# Sheet1.net
KiCad netlist of a schematic drawn in Altium Designer
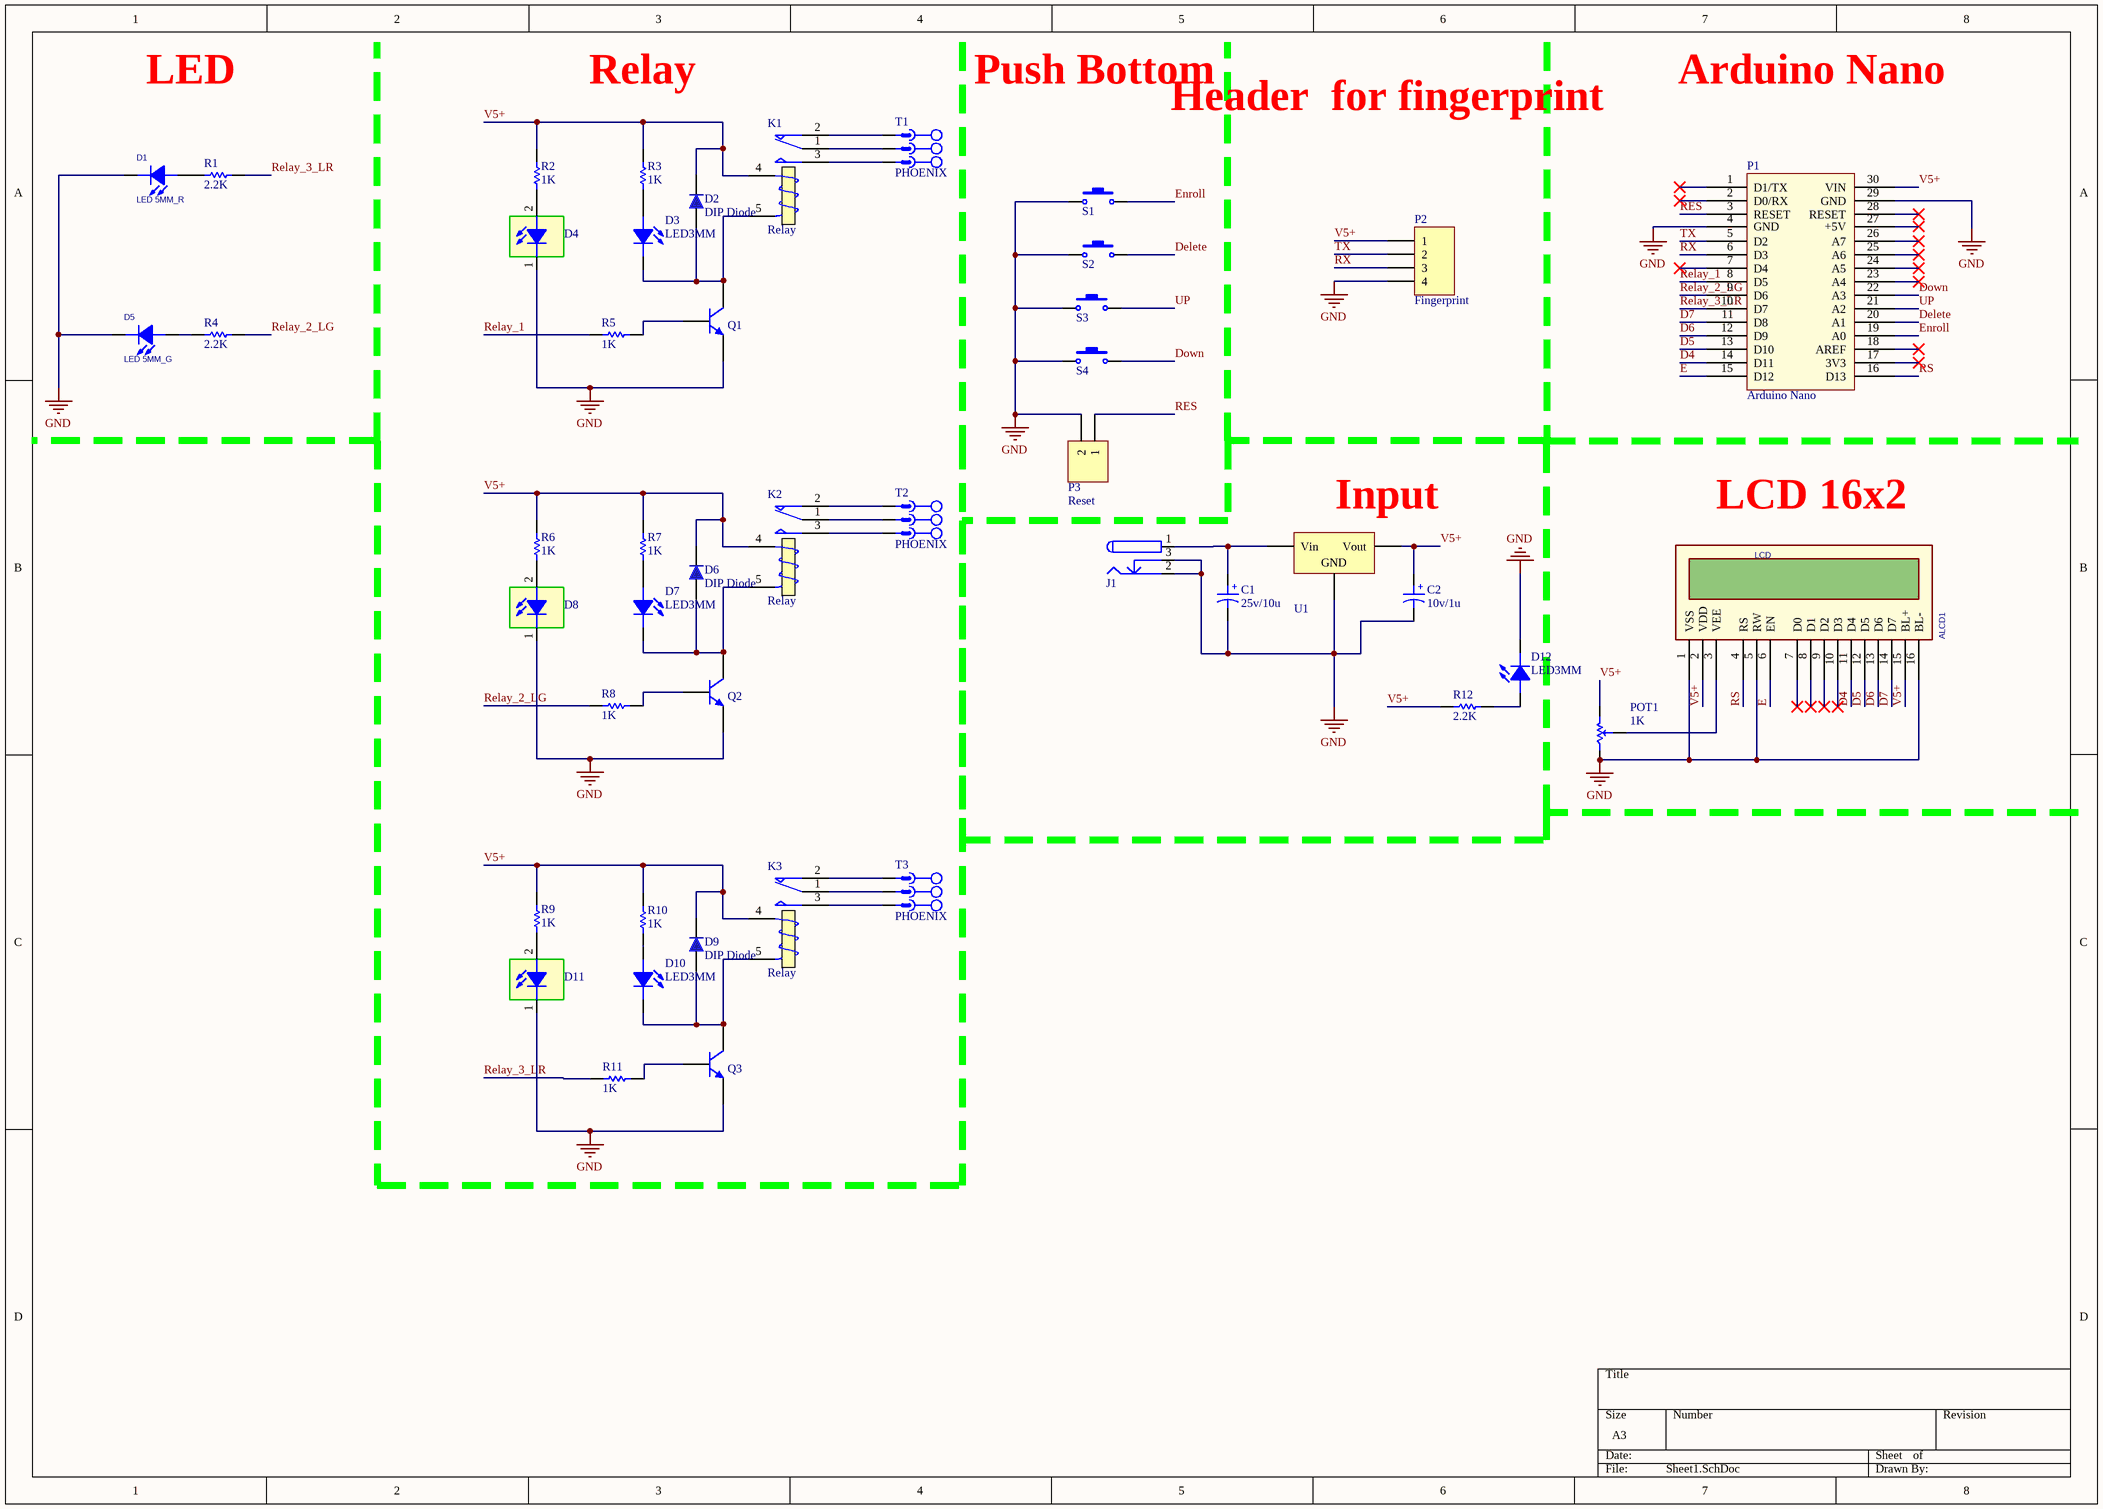
[diagram p0: Sheet1.SchDoc]

(export (version "E")
  (design (tool "Eeschema 10.0.6"))
  (components
    (comp (ref "ALCD1")
      (value "LCD")
      (footprint "LCD_2X16 BLUE - 2.5mm")
      (description "Alphanumic LCD")
      (fields (field (name "DESIGNER") "Abbas Basereh"))
      (libsource (lib "Altium") (part "LCD"))
    )
    (comp (ref "C1")
      (value "25v/10u")
      (footprint "Cap electrolitic radial 5x11-2")
      (description "Cap electrolitic radial")
      (fields (field (name "DESIGNER") "Abbas Basereh"))
      (libsource (lib "Altium") (part "Cap ELECTROLITIC TOTAL SIZE"))
    )
    (comp (ref "C2")
      (value "10v/1u")
      (footprint "Cap electrolitic radial 5x11-2")
      (description "Cap electrolitic radial")
      (fields (field (name "DESIGNER") "Abbas Basereh"))
      (libsource (lib "Altium") (part "Cap ELECTROLITIC TOTAL SIZE"))
    )
    (comp (ref "D1")
      (value "LED 5MM_R")
      (footprint "LED5MM_RED")
      (description "Light Emitting Diode")
      (fields (field (name "DESIGNER") "Abbas Basereh"))
      (libsource (lib "Altium") (part "LED 5MM"))
    )
    (comp (ref "D2")
      (value "DIP Diode")
      (footprint "Diode 1n4007")
      (description "Diode DIP Package")
      (fields (field (name "PUBLISHER") "Altium Limited"))
      (libsource (lib "Altium") (part "Diode DIP Package"))
    )
    (comp (ref "D3")
      (value "LED3MM")
      (footprint "LED3mm_GRN")
      (description "Light Emitting Diode")
      (fields (field (name "DESIGNER") "Ali Hafizi"))
      (libsource (lib "Altium") (part "LED 3MM"))
    )
    (comp (ref "D4")
      (value "LED SMD 3528")
      (footprint "LED 3528")
      (description "SMD 3528 LED")
      (libsource (lib "Altium") (part "LED SMD 3528"))
    )
    (comp (ref "D5")
      (value "LED 5MM_G")
      (footprint "LED5MM_GRN")
      (description "Light Emitting Diode")
      (fields (field (name "DESIGNER") "Abbas Basereh"))
      (libsource (lib "Altium") (part "LED 5MM"))
    )
    (comp (ref "D6")
      (value "DIP Diode")
      (footprint "Diode 1n4007")
      (description "Diode DIP Package")
      (fields (field (name "PUBLISHER") "Altium Limited"))
      (libsource (lib "Altium") (part "Diode DIP Package"))
    )
    (comp (ref "D7")
      (value "LED3MM")
      (footprint "LED3mm_GRN")
      (description "Light Emitting Diode")
      (fields (field (name "DESIGNER") "Ali Hafizi"))
      (libsource (lib "Altium") (part "LED 3MM"))
    )
    (comp (ref "D8")
      (value "LED SMD 3528")
      (footprint "LED 3528")
      (description "SMD 3528 LED")
      (libsource (lib "Altium") (part "LED SMD 3528"))
    )
    (comp (ref "D9")
      (value "DIP Diode")
      (footprint "Diode 1n4007")
      (description "Diode DIP Package")
      (fields (field (name "PUBLISHER") "Altium Limited"))
      (libsource (lib "Altium") (part "Diode DIP Package"))
    )
    (comp (ref "D10")
      (value "LED3MM")
      (footprint "LED3mm_GRN")
      (description "Light Emitting Diode")
      (fields (field (name "DESIGNER") "Ali Hafizi"))
      (libsource (lib "Altium") (part "LED 3MM"))
    )
    (comp (ref "D11")
      (value "LED SMD 3528")
      (footprint "LED 3528")
      (description "SMD 3528 LED")
      (libsource (lib "Altium") (part "LED SMD 3528"))
    )
    (comp (ref "D12")
      (value "LED3MM")
      (footprint "LED5MM_RED")
      (description "Light Emitting Diode")
      (fields (field (name "DESIGNER") "Ali Hafizi"))
      (libsource (lib "Altium") (part "LED 3MM"))
    )
    (comp (ref "J1")
      (value "DC Power Jack")
      (footprint "DC Power Jack 1")
      (description "DC Power Jack. Center Pin 2.5mm. Diameter: 5.7mm")
      (fields (field (name "DESIGNER") "Ali Hafizi"))
      (libsource (lib "Altium") (part "DC Power Jack"))
    )
    (comp (ref "K1")
      (value "Relay")
      (footprint "Relay 15.40x12.10x13.10")
      (description "Relay_SPDT POWER NEEDLE")
      (fields (field (name "DESIGNER") "Ali Hafizi"))
      (libsource (lib "Altium") (part "RELAY General"))
    )
    (comp (ref "K2")
      (value "Relay")
      (footprint "Relay 15.40x12.10x13.10")
      (description "Relay_SPDT POWER NEEDLE")
      (fields (field (name "DESIGNER") "Ali Hafizi"))
      (libsource (lib "Altium") (part "RELAY General"))
    )
    (comp (ref "K3")
      (value "Relay")
      (footprint "Relay 15.40x12.10x13.10")
      (description "Relay_SPDT POWER NEEDLE")
      (fields (field (name "DESIGNER") "Ali Hafizi"))
      (libsource (lib "Altium") (part "RELAY General"))
    )
    (comp (ref "P1")
      (value "Arduino Nano")
      (footprint "Arduino Nano")
      (libsource (lib "Arduino") (part "Arduino Nano"))
    )
    (comp (ref "P2")
      (value "Fingerprint")
      (footprint "HDR1X4")
      (description "Header, 4-Pin")
      (fields (field (name "PUBLISHER") "Altium Limited"))
      (libsource (lib "Altium") (part "Header 4"))
    )
    (comp (ref "P3")
      (value "Reset")
      (footprint "HDR1X2")
      (description "Header, 2-Pin")
      (fields (field (name "PUBLISHER") "Altium Limited"))
      (libsource (lib "Altium") (part "Header 2"))
    )
    (comp (ref "POT1")
      (value "1K")
      (footprint "POT 1")
      (description "Variable Resistor")
      (libsource (lib "Altium") (part "POT"))
    )
    (comp (ref "Q1")
      (value "BC547")
      (footprint "TO-92 BENT")
      (description "NPN General-purpose Transistor")
      (fields (field (name "DESIGNER") "Abbas Basereh"))
      (libsource (lib "Altium") (part "BC547"))
    )
    (comp (ref "Q2")
      (value "BC547")
      (footprint "TO-92 BENT")
      (description "NPN General-purpose Transistor")
      (fields (field (name "DESIGNER") "Abbas Basereh"))
      (libsource (lib "Altium") (part "BC547"))
    )
    (comp (ref "Q3")
      (value "BC547")
      (footprint "TO-92 BENT")
      (description "NPN General-purpose Transistor")
      (fields (field (name "DESIGNER") "Abbas Basereh"))
      (libsource (lib "Altium") (part "BC547"))
    )
    (comp (ref "R1")
      (value "2.2K")
      (footprint "Axial 0_25w_2_54mm")
      (description "RES Axial 0.25W")
      (fields (field (name "DESIGNER") "Abbas Basereh"))
      (libsource (lib "Altium") (part "RES Axial 0.25W"))
    )
    (comp (ref "R2")
      (value "1K")
      (footprint "Axial 0_25w_2_54mm")
      (description "RES Axial 0.25W")
      (fields (field (name "DESIGNER") "Abbas Basereh"))
      (libsource (lib "Altium") (part "RES Axial 0.25W"))
    )
    (comp (ref "R3")
      (value "1K")
      (footprint "Axial 0_25w_2_54mm")
      (description "RES Axial 0.25W")
      (fields (field (name "DESIGNER") "Abbas Basereh"))
      (libsource (lib "Altium") (part "RES Axial 0.25W"))
    )
    (comp (ref "R4")
      (value "2.2K")
      (footprint "Axial 0_25w_2_54mm")
      (description "RES Axial 0.25W")
      (fields (field (name "DESIGNER") "Abbas Basereh"))
      (libsource (lib "Altium") (part "RES Axial 0.25W"))
    )
    (comp (ref "R5")
      (value "1K")
      (footprint "Axial 0_25w_2_54mm")
      (description "RES Axial 0.25W")
      (fields (field (name "DESIGNER") "Abbas Basereh"))
      (libsource (lib "Altium") (part "RES Axial 0.25W"))
    )
    (comp (ref "R6")
      (value "1K")
      (footprint "Axial 0_25w_2_54mm")
      (description "RES Axial 0.25W")
      (fields (field (name "DESIGNER") "Abbas Basereh"))
      (libsource (lib "Altium") (part "RES Axial 0.25W"))
    )
    (comp (ref "R7")
      (value "1K")
      (footprint "Axial 0_25w_2_54mm")
      (description "RES Axial 0.25W")
      (fields (field (name "DESIGNER") "Abbas Basereh"))
      (libsource (lib "Altium") (part "RES Axial 0.25W"))
    )
    (comp (ref "R8")
      (value "1K")
      (footprint "Axial 0_25w_2_54mm")
      (description "RES Axial 0.25W")
      (fields (field (name "DESIGNER") "Abbas Basereh"))
      (libsource (lib "Altium") (part "RES Axial 0.25W"))
    )
    (comp (ref "R9")
      (value "1K")
      (footprint "Axial 0_25w_2_54mm")
      (description "RES Axial 0.25W")
      (fields (field (name "DESIGNER") "Abbas Basereh"))
      (libsource (lib "Altium") (part "RES Axial 0.25W"))
    )
    (comp (ref "R10")
      (value "1K")
      (footprint "Axial 0_25w_2_54mm")
      (description "RES Axial 0.25W")
      (fields (field (name "DESIGNER") "Abbas Basereh"))
      (libsource (lib "Altium") (part "RES Axial 0.25W"))
    )
    (comp (ref "R11")
      (value "1K")
      (footprint "Axial 0_25w_2_54mm")
      (description "RES Axial 0.25W")
      (fields (field (name "DESIGNER") "Abbas Basereh"))
      (libsource (lib "Altium") (part "RES Axial 0.25W"))
    )
    (comp (ref "R12")
      (value "2.2K")
      (footprint "Axial 0_25w_2_54mm")
      (description "RES Axial 0.25W")
      (fields (field (name "DESIGNER") "Abbas Basereh"))
      (libsource (lib "Altium") (part "RES Axial 0.25W"))
    )
    (comp (ref "S1")
      (value "Switch PB")
      (footprint "Switch - Push to On")
      (description "Push Button Switch")
      (libsource (lib "Altium") (part "Switch PB"))
    )
    (comp (ref "S2")
      (value "Switch PB")
      (footprint "Switch - Push to On")
      (description "Push Button Switch")
      (libsource (lib "Altium") (part "Switch PB"))
    )
    (comp (ref "S3")
      (value "Switch PB")
      (footprint "Switch - Push to On")
      (description "Push Button Switch")
      (libsource (lib "Altium") (part "Switch PB"))
    )
    (comp (ref "S4")
      (value "Switch PB")
      (footprint "Switch - Push to On")
      (description "Push Button Switch")
      (libsource (lib "Altium") (part "Switch PB"))
    )
    (comp (ref "T1")
      (value "PHOENIX")
      (footprint "MSTBV 2,5/3-G-5")
      (description "3 Pitch: 5 mm Color: green Contact surface: Tin Assembly")
      (fields
        (field (name "MANUFACTURER") "PHOENIX CONTACT")
        (field (name "VOLTAGE") "320 V")
        (field (name "DESIGNER") "ABBAS BASEREH")
      )
      (libsource (lib "Altium") (part "CON_Phoenix_MSTBV_03"))
    )
    (comp (ref "T2")
      (value "PHOENIX")
      (footprint "MSTBV 2,5/3-G-5")
      (description "3 Pitch: 5 mm Color: green Contact surface: Tin Assembly")
      (fields
        (field (name "MANUFACTURER") "PHOENIX CONTACT")
        (field (name "VOLTAGE") "320 V")
        (field (name "DESIGNER") "ABBAS BASEREH")
      )
      (libsource (lib "Altium") (part "CON_Phoenix_MSTBV_03"))
    )
    (comp (ref "T3")
      (value "PHOENIX")
      (footprint "MSTBV 2,5/3-G-5")
      (description "3 Pitch: 5 mm Color: green Contact surface: Tin Assembly")
      (fields
        (field (name "MANUFACTURER") "PHOENIX CONTACT")
        (field (name "VOLTAGE") "320 V")
        (field (name "DESIGNER") "ABBAS BASEREH")
      )
      (libsource (lib "Altium") (part "CON_Phoenix_MSTBV_03"))
    )
    (comp (ref "U1")
      (value "L7805CV")
      (footprint "TO-220 AB with heatsink ya25")
      (description "Linear Voltage Regulator IC Positive FIXED Output 5V 1.5A TO-220AB")
      (fields (field (name "MANUFACTURER") "STMicroelectronics") (field (name "DESIGNER") "Abbas Basereh"))
      (libsource (lib "Altium") (part "L7805CV-Linear Voltage Regulator"))
    )
  )
  (nets
    (net (code "1") (name "/D4") (class "Default")
      (node (ref "ALCD1") (pin "11") (pinfunction "D4_11") (pintype "passive"))
      (node (ref "P1") (pin "14") (pinfunction "D11_14") (pintype "passive"))
    )
    (net (code "2") (name "/D5") (class "Default")
      (node (ref "ALCD1") (pin "12") (pinfunction "D5_12") (pintype "passive"))
      (node (ref "P1") (pin "13") (pinfunction "D10_13") (pintype "passive"))
    )
    (net (code "3") (name "/D6") (class "Default")
      (node (ref "ALCD1") (pin "13") (pinfunction "D6_13") (pintype "passive"))
      (node (ref "P1") (pin "12") (pinfunction "D9_12") (pintype "passive"))
    )
    (net (code "4") (name "/D7") (class "Default")
      (node (ref "ALCD1") (pin "14") (pinfunction "D7_14") (pintype "passive"))
      (node (ref "P1") (pin "11") (pinfunction "D8_11") (pintype "passive"))
    )
    (net (code "5") (name "/Delete") (class "Default")
      (node (ref "P1") (pin "20") (pinfunction "A1_20") (pintype "passive"))
      (node (ref "S2") (pin "2") (pinfunction "2_2") (pintype "passive"))
    )
    (net (code "6") (name "/Down") (class "Default")
      (node (ref "P1") (pin "22") (pinfunction "A3_22") (pintype "passive"))
      (node (ref "S4") (pin "2") (pinfunction "2_2") (pintype "passive"))
    )
    (net (code "7") (name "/E") (class "Default")
      (node (ref "ALCD1") (pin "6") (pinfunction "EN_6") (pintype "passive"))
      (node (ref "P1") (pin "15") (pinfunction "D12_15") (pintype "passive"))
    )
    (net (code "8") (name "/Enroll") (class "Default")
      (node (ref "P1") (pin "19") (pinfunction "A0_19") (pintype "passive"))
      (node (ref "S1") (pin "2") (pinfunction "2_2") (pintype "passive"))
    )
    (net (code "9") (name "/RES") (class "Default")
      (node (ref "P1") (pin "3") (pinfunction "RESET_3") (pintype "passive"))
      (node (ref "P3") (pin "1") (pinfunction "1_1") (pintype "passive"))
    )
    (net (code "10") (name "/RS") (class "Default")
      (node (ref "ALCD1") (pin "4") (pinfunction "RS_4") (pintype "passive"))
      (node (ref "P1") (pin "16") (pinfunction "D13_16") (pintype "passive"))
    )
    (net (code "11") (name "/RX") (class "Default")
      (node (ref "P1") (pin "6") (pinfunction "D3_6") (pintype "passive"))
      (node (ref "P2") (pin "3") (pinfunction "3_3") (pintype "passive"))
    )
    (net (code "12") (name "/Relay_1") (class "Default")
      (node (ref "P1") (pin "8") (pinfunction "D5_8") (pintype "passive"))
      (node (ref "R5") (pin "2") (pinfunction "2_2") (pintype "passive"))
    )
    (net (code "13") (name "/Relay_2_LG") (class "Default")
      (node (ref "P1") (pin "9") (pinfunction "D6_9") (pintype "passive"))
      (node (ref "R4") (pin "2") (pinfunction "2_2") (pintype "passive"))
      (node (ref "R8") (pin "1") (pinfunction "1_1") (pintype "passive"))
    )
    (net (code "14") (name "/Relay_3_LR") (class "Default")
      (node (ref "P1") (pin "10") (pinfunction "D7_10") (pintype "passive"))
      (node (ref "R1") (pin "2") (pinfunction "2_2") (pintype "passive"))
      (node (ref "R11") (pin "2") (pinfunction "2_2") (pintype "passive"))
    )
    (net (code "15") (name "/TX") (class "Default")
      (node (ref "P1") (pin "5") (pinfunction "D2_5") (pintype "passive"))
      (node (ref "P2") (pin "2") (pinfunction "2_2") (pintype "passive"))
    )
    (net (code "16") (name "/UP") (class "Default")
      (node (ref "P1") (pin "21") (pinfunction "A2_21") (pintype "passive"))
      (node (ref "S3") (pin "2") (pinfunction "2_2") (pintype "passive"))
    )
    (net (code "17") (name "/V5+") (class "Default")
      (node (ref "ALCD1") (pin "15") (pinfunction "BL+_15") (pintype "passive"))
      (node (ref "ALCD1") (pin "2") (pinfunction "VDD_2") (pintype "passive"))
      (node (ref "C2") (pin "1") (pinfunction "1_1") (pintype "passive"))
      (node (ref "D2") (pin "2") (pintype "passive"))
      (node (ref "D6") (pin "2") (pintype "passive"))
      (node (ref "D9") (pin "2") (pintype "passive"))
      (node (ref "K1") (pin "4") (pinfunction "T1_4") (pintype "passive"))
      (node (ref "K2") (pin "4") (pinfunction "T1_4") (pintype "passive"))
      (node (ref "K3") (pin "4") (pinfunction "T1_4") (pintype "passive"))
      (node (ref "P1") (pin "30") (pinfunction "VIN_30") (pintype "passive"))
      (node (ref "P2") (pin "1") (pinfunction "1_1") (pintype "passive"))
      (node (ref "POT1") (pin "2") (pinfunction "CW_2") (pintype "passive"))
      (node (ref "R10") (pin "2") (pinfunction "2_2") (pintype "passive"))
      (node (ref "R12") (pin "1") (pinfunction "1_1") (pintype "passive"))
      (node (ref "R2") (pin "2") (pinfunction "2_2") (pintype "passive"))
      (node (ref "R3") (pin "2") (pinfunction "2_2") (pintype "passive"))
      (node (ref "R6") (pin "1") (pinfunction "1_1") (pintype "passive"))
      (node (ref "R7") (pin "1") (pinfunction "1_1") (pintype "passive"))
      (node (ref "R9") (pin "2") (pinfunction "2_2") (pintype "passive"))
      (node (ref "U1") (pin "3") (pinfunction "Vout_3") (pintype "passive"))
    )
    (net (code "18") (name "GND") (class "Default")
      (node (ref "ALCD1") (pin "1") (pinfunction "VSS_1") (pintype "passive"))
      (node (ref "ALCD1") (pin "16") (pinfunction "BL-_16") (pintype "passive"))
      (node (ref "ALCD1") (pin "5") (pinfunction "RW_5") (pintype "passive"))
      (node (ref "C1") (pin "2") (pinfunction "2_2") (pintype "passive"))
      (node (ref "C2") (pin "2") (pinfunction "2_2") (pintype "passive"))
      (node (ref "D1") (pin "2") (pinfunction "CATHODE_2") (pintype "passive"))
      (node (ref "D11") (pin "1") (pinfunction "1_1") (pintype "passive"))
      (node (ref "D12") (pin "2") (pinfunction "CATHODE_2") (pintype "passive"))
      (node (ref "D4") (pin "1") (pinfunction "1_1") (pintype "passive"))
      (node (ref "D5") (pin "2") (pinfunction "CATHODE_2") (pintype "passive"))
      (node (ref "D8") (pin "1") (pinfunction "1_1") (pintype "passive"))
      (node (ref "J1") (pin "2") (pinfunction "2_2") (pintype "power_in"))
      (node (ref "J1") (pin "3") (pinfunction "3_3") (pintype "power_in"))
      (node (ref "P1") (pin "29") (pinfunction "GND_29") (pintype "passive"))
      (node (ref "P1") (pin "4") (pinfunction "GND_4") (pintype "passive"))
      (node (ref "P2") (pin "4") (pinfunction "4_4") (pintype "passive"))
      (node (ref "P3") (pin "2") (pinfunction "2_2") (pintype "passive"))
      (node (ref "POT1") (pin "1") (pinfunction "CCW_1") (pintype "passive"))
      (node (ref "Q1") (pin "3") (pinfunction "E_3") (pintype "passive"))
      (node (ref "Q2") (pin "3") (pinfunction "E_3") (pintype "passive"))
      (node (ref "Q3") (pin "3") (pinfunction "E_3") (pintype "passive"))
      (node (ref "S1") (pin "1") (pinfunction "1_1") (pintype "passive"))
      (node (ref "S2") (pin "1") (pinfunction "1_1") (pintype "passive"))
      (node (ref "S3") (pin "1") (pinfunction "1_1") (pintype "passive"))
      (node (ref "S4") (pin "1") (pinfunction "1_1") (pintype "passive"))
      (node (ref "U1") (pin "2") (pinfunction "GND_2") (pintype "passive"))
    )
    (net (code "19") (name "Net-(ALCD1-VEE)") (class "Default")
      (node (ref "ALCD1") (pin "3") (pinfunction "VEE_3") (pintype "passive"))
      (node (ref "POT1") (pin "3") (pinfunction "SetPoint_3") (pintype "passive"))
    )
    (net (code "20") (name "Net-(D1-ANODE)") (class "Default")
      (node (ref "D1") (pin "1") (pinfunction "ANODE_1") (pintype "passive"))
      (node (ref "R1") (pin "1") (pinfunction "1_1") (pintype "passive"))
    )
    (net (code "21") (name "Net-(D3-ANODE)") (class "Default")
      (node (ref "D3") (pin "1") (pinfunction "ANODE_1") (pintype "passive"))
      (node (ref "R3") (pin "1") (pinfunction "1_1") (pintype "passive"))
    )
    (net (code "22") (name "Net-(D3-CATHODE)") (class "Default")
      (node (ref "D2") (pin "1") (pintype "passive"))
      (node (ref "D3") (pin "2") (pinfunction "CATHODE_2") (pintype "passive"))
      (node (ref "K1") (pin "5") (pinfunction "T2_5") (pintype "passive"))
      (node (ref "Q1") (pin "1") (pinfunction "C_1") (pintype "passive"))
    )
    (net (code "23") (name "Net-(D4-Pad2)") (class "Default")
      (node (ref "D4") (pin "2") (pinfunction "2_2") (pintype "passive"))
      (node (ref "R2") (pin "1") (pinfunction "1_1") (pintype "passive"))
    )
    (net (code "24") (name "Net-(D5-ANODE)") (class "Default")
      (node (ref "D5") (pin "1") (pinfunction "ANODE_1") (pintype "passive"))
      (node (ref "R4") (pin "1") (pinfunction "1_1") (pintype "passive"))
    )
    (net (code "25") (name "Net-(D7-ANODE)") (class "Default")
      (node (ref "D7") (pin "1") (pinfunction "ANODE_1") (pintype "passive"))
      (node (ref "R7") (pin "2") (pinfunction "2_2") (pintype "passive"))
    )
    (net (code "26") (name "Net-(D7-CATHODE)") (class "Default")
      (node (ref "D6") (pin "1") (pintype "passive"))
      (node (ref "D7") (pin "2") (pinfunction "CATHODE_2") (pintype "passive"))
      (node (ref "K2") (pin "5") (pinfunction "T2_5") (pintype "passive"))
      (node (ref "Q2") (pin "1") (pinfunction "C_1") (pintype "passive"))
    )
    (net (code "27") (name "Net-(D8-Pad2)") (class "Default")
      (node (ref "D8") (pin "2") (pinfunction "2_2") (pintype "passive"))
      (node (ref "R6") (pin "2") (pinfunction "2_2") (pintype "passive"))
    )
    (net (code "28") (name "Net-(D10-ANODE)") (class "Default")
      (node (ref "D10") (pin "1") (pinfunction "ANODE_1") (pintype "passive"))
      (node (ref "R10") (pin "1") (pinfunction "1_1") (pintype "passive"))
    )
    (net (code "29") (name "Net-(D10-CATHODE)") (class "Default")
      (node (ref "D10") (pin "2") (pinfunction "CATHODE_2") (pintype "passive"))
      (node (ref "D9") (pin "1") (pintype "passive"))
      (node (ref "K3") (pin "5") (pinfunction "T2_5") (pintype "passive"))
      (node (ref "Q3") (pin "1") (pinfunction "C_1") (pintype "passive"))
    )
    (net (code "30") (name "Net-(D11-Pad2)") (class "Default")
      (node (ref "D11") (pin "2") (pinfunction "2_2") (pintype "passive"))
      (node (ref "R9") (pin "1") (pinfunction "1_1") (pintype "passive"))
    )
    (net (code "31") (name "Net-(D12-ANODE)") (class "Default")
      (node (ref "D12") (pin "1") (pinfunction "ANODE_1") (pintype "passive"))
      (node (ref "R12") (pin "2") (pinfunction "2_2") (pintype "passive"))
    )
    (net (code "32") (name "Net-(K1-COM)") (class "Default")
      (node (ref "K1") (pin "1") (pinfunction "COM_1") (pintype "passive"))
      (node (ref "T1") (pin "2") (pinfunction "2_2") (pintype "passive"))
    )
    (net (code "33") (name "Net-(K1-NC)") (class "Default")
      (node (ref "K1") (pin "2") (pinfunction "NC_2") (pintype "passive"))
      (node (ref "T1") (pin "1") (pinfunction "1_1") (pintype "passive"))
    )
    (net (code "34") (name "Net-(K1-NO)") (class "Default")
      (node (ref "K1") (pin "3") (pinfunction "NO_3") (pintype "passive"))
      (node (ref "T1") (pin "3") (pinfunction "3_3") (pintype "passive"))
    )
    (net (code "35") (name "Net-(K2-COM)") (class "Default")
      (node (ref "K2") (pin "1") (pinfunction "COM_1") (pintype "passive"))
      (node (ref "T2") (pin "2") (pinfunction "2_2") (pintype "passive"))
    )
    (net (code "36") (name "Net-(K2-NC)") (class "Default")
      (node (ref "K2") (pin "2") (pinfunction "NC_2") (pintype "passive"))
      (node (ref "T2") (pin "1") (pinfunction "1_1") (pintype "passive"))
    )
    (net (code "37") (name "Net-(K2-NO)") (class "Default")
      (node (ref "K2") (pin "3") (pinfunction "NO_3") (pintype "passive"))
      (node (ref "T2") (pin "3") (pinfunction "3_3") (pintype "passive"))
    )
    (net (code "38") (name "Net-(K3-COM)") (class "Default")
      (node (ref "K3") (pin "1") (pinfunction "COM_1") (pintype "passive"))
      (node (ref "T3") (pin "2") (pinfunction "2_2") (pintype "passive"))
    )
    (net (code "39") (name "Net-(K3-NC)") (class "Default")
      (node (ref "K3") (pin "2") (pinfunction "NC_2") (pintype "passive"))
      (node (ref "T3") (pin "1") (pinfunction "1_1") (pintype "passive"))
    )
    (net (code "40") (name "Net-(K3-NO)") (class "Default")
      (node (ref "K3") (pin "3") (pinfunction "NO_3") (pintype "passive"))
      (node (ref "T3") (pin "3") (pinfunction "3_3") (pintype "passive"))
    )
    (net (code "41") (name "Net-(Q1-B)") (class "Default")
      (node (ref "Q1") (pin "2") (pinfunction "B_2") (pintype "passive"))
      (node (ref "R5") (pin "1") (pinfunction "1_1") (pintype "passive"))
    )
    (net (code "42") (name "Net-(Q2-B)") (class "Default")
      (node (ref "Q2") (pin "2") (pinfunction "B_2") (pintype "passive"))
      (node (ref "R8") (pin "2") (pinfunction "2_2") (pintype "passive"))
    )
    (net (code "43") (name "Net-(Q3-B)") (class "Default")
      (node (ref "Q3") (pin "2") (pinfunction "B_2") (pintype "passive"))
      (node (ref "R11") (pin "1") (pinfunction "1_1") (pintype "passive"))
    )
    (net (code "44") (name "Net-(U1-Vin)") (class "Default")
      (node (ref "C1") (pin "1") (pinfunction "1_1") (pintype "passive"))
      (node (ref "J1") (pin "1") (pinfunction "1_1") (pintype "power_in"))
      (node (ref "U1") (pin "1") (pinfunction "Vin_1") (pintype "passive"))
    )
    (net (code "45") (name "unconnected-(ALCD1-D0-Pad7)") (class "Default")
      (node (ref "ALCD1") (pin "7") (pinfunction "D0_7") (pintype "passive+no_connect"))
    )
    (net (code "46") (name "unconnected-(ALCD1-D1-Pad8)") (class "Default")
      (node (ref "ALCD1") (pin "8") (pinfunction "D1_8") (pintype "passive+no_connect"))
    )
    (net (code "47") (name "unconnected-(ALCD1-D2-Pad9)") (class "Default")
      (node (ref "ALCD1") (pin "9") (pinfunction "D2_9") (pintype "passive+no_connect"))
    )
    (net (code "48") (name "unconnected-(ALCD1-D3-Pad10)") (class "Default")
      (node (ref "ALCD1") (pin "10") (pinfunction "D3_10") (pintype "passive+no_connect"))
    )
    (net (code "49") (name "unconnected-(P1-+5V-Pad27)") (class "Default")
      (node (ref "P1") (pin "27") (pinfunction "+5V_27") (pintype "passive+no_connect"))
    )
    (net (code "50") (name "unconnected-(P1-3V3-Pad17)") (class "Default")
      (node (ref "P1") (pin "17") (pinfunction "3V3_17") (pintype "passive+no_connect"))
    )
    (net (code "51") (name "unconnected-(P1-A4-Pad23)") (class "Default")
      (node (ref "P1") (pin "23") (pinfunction "A4_23") (pintype "passive+no_connect"))
    )
    (net (code "52") (name "unconnected-(P1-A5-Pad24)") (class "Default")
      (node (ref "P1") (pin "24") (pinfunction "A5_24") (pintype "passive+no_connect"))
    )
    (net (code "53") (name "unconnected-(P1-A6-Pad25)") (class "Default")
      (node (ref "P1") (pin "25") (pinfunction "A6_25") (pintype "passive+no_connect"))
    )
    (net (code "54") (name "unconnected-(P1-A7-Pad26)") (class "Default")
      (node (ref "P1") (pin "26") (pinfunction "A7_26") (pintype "passive+no_connect"))
    )
    (net (code "55") (name "unconnected-(P1-AREF-Pad18)") (class "Default")
      (node (ref "P1") (pin "18") (pinfunction "AREF_18") (pintype "passive+no_connect"))
    )
    (net (code "56") (name "unconnected-(P1-D0{slash}RX-Pad2)") (class "Default")
      (node (ref "P1") (pin "2") (pinfunction "D0/RX_2") (pintype "passive+no_connect"))
    )
    (net (code "57") (name "unconnected-(P1-D1{slash}TX-Pad1)") (class "Default")
      (node (ref "P1") (pin "1") (pinfunction "D1/TX_1") (pintype "passive+no_connect"))
    )
    (net (code "58") (name "unconnected-(P1-D4-Pad7)") (class "Default")
      (node (ref "P1") (pin "7") (pinfunction "D4_7") (pintype "passive+no_connect"))
    )
    (net (code "59") (name "unconnected-(P1-RESET-Pad28)") (class "Default")
      (node (ref "P1") (pin "28") (pinfunction "RESET_28") (pintype "passive+no_connect"))
    )
  )
)
